# usb_to_rs232.net
KiCad netlist of a schematic drawn in Altium Designer
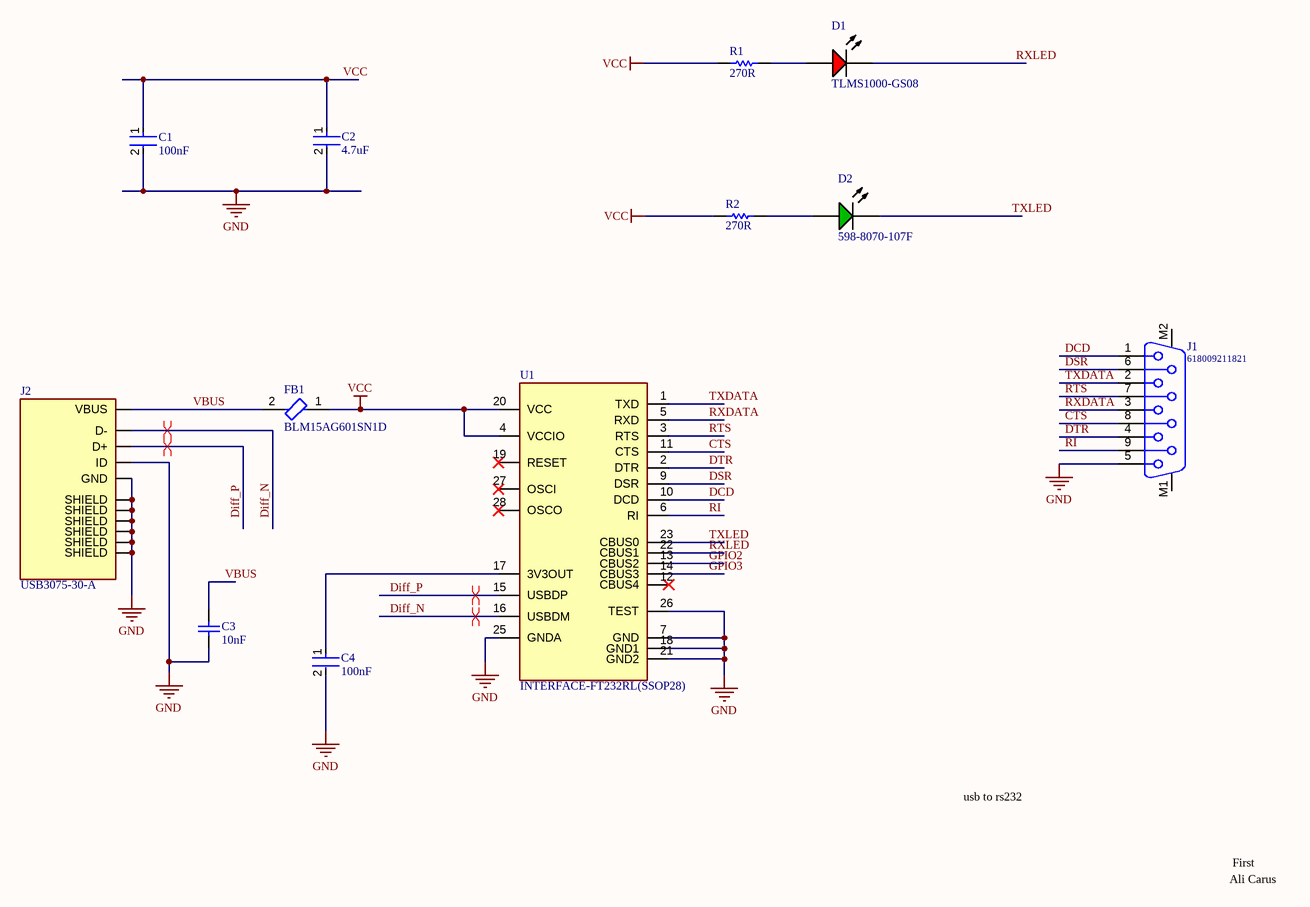
[diagram p0: usb_to_rs232.SchDoc]

(export (version "E")
  (design (tool "Eeschema 10.0.6"))
  (components
    (comp (ref "C1")
      (value "100nF")
      (footprint "FP-CGA3E-0_3-0_1-IPC_A")
      (description "Cap Ceramic 100nF 100V X7S 10% Pad SMD 0603 +125°C Automotive T/R")
      (fields (field (name "TOLERANCE") "10%"))
      (libsource (lib "Altium Content Vault") (part "b4654b650e69147ec39a6b967a45e02"))
    )
    (comp (ref "C2")
      (value "4.7uF")
      (footprint "FP-GRM188-0_2-MFG")
      (description "Chip Multilayer Ceramic Capacitors for General Purpose, 0603, 4.7uF, X5R, 15%, 10%, 35V")
      (fields (field (name "VOLTAGE") "35V") (field (name "TOLERANCE") "10%"))
      (libsource (lib "Altium Content Vault") (part "11868f565c42a9108669ba33697ecf6"))
    )
    (comp (ref "C3")
      (value "10nF")
      (footprint "CAPC1608X90X35ML10T15")
      (description "Chip Capacitor, 10 nF, +/- 10%, 50 V, -55 to 125 degC, 0603 (1608 Metric), RoHS, Tape and Reel")
      (fields (field (name "VOLTAGE") "50V") (field (name "TOLERANCE") "10%"))
      (libsource (lib "Altium Content Vault") (part "CAP-NP-2"))
    )
    (comp (ref "C4")
      (value "100nF")
      (footprint "FP-CGA3E-0_3-0_1-IPC_A")
      (description "Cap Ceramic 100nF 100V X7S 10% Pad SMD 0603 +125°C Automotive T/R")
      (fields (field (name "TOLERANCE") "10%"))
      (libsource (lib "Altium Content Vault") (part "b4654b650e69147ec39a6b967a45e02"))
    )
    (comp (ref "D1")
      (value "TLMS1000-GS08")
      (footprint "VISH-TLMS1000_V")
      (description "Low Current LED, 40 mW, 1.8 V, -40 to 100 degC, 2-Pin SMD (0603), RoHS, Tape and Reel")
      (fields (field (name "MANUFACTURER") "Vishay"))
      (libsource (lib "Altium Content Vault") (part "LED-RED-AK-2"))
    )
    (comp (ref "D2")
      (value "598-8070-107F")
      (footprint "DIAL-0603-2_V")
      (description "Single Color LED, 2 V, -30 to 85 degC, 2-Pin SMD (0603), RoHS, Tape and Reel")
      (fields (field (name "MANUFACTURER") "Dialight"))
      (libsource (lib "Altium Content Vault") (part "LED-GREEN-KA-2"))
    )
    (comp (ref "FB1")
      (value "BLM15AG601SN1D")
      (footprint "FP-BLM15-0_05-MFG")
      (description "Chip Ferrite Bead, 0402, 600Ω @ 100MHz, 0.52Ω, 25%, 300mA")
      (fields (field (name "TOLERANCE") "25%"))
      (libsource (lib "Altium Content Vault") (part "5f30dd21d616792df468990f7003faa"))
    )
    (comp (ref "J1")
      (value "618009211821")
      (footprint "618009211821")
      (description "WR-DSUB 8.08mm Female PCB Connector without Hex Screw, Angled, 9p")
      (fields (field (name "MANUFACTURER") "Wurth Elektronik"))
      (libsource (lib "usb_to_rs232") (part "618009211821"))
    )
    (comp (ref "J2")
      (value "USB3075-30-A")
      (footprint "GCT_USB3075-30-A")
      (description "USB - micro B USB 2.0 Receptacle Connector 5 Position Surface Mount, Right Angle; Through Hole")
      (fields
        (field (name "MF") "Global Connector Technology")
        (field (name "DIGI-KEY_PART_NUMBER") "2073-USB3075-30-ACT-ND")
      )
      (libsource (lib "usb_to_rs232") (part "USB3075-30-A"))
    )
    (comp (ref "R1")
      (value "270R")
      (footprint "RESC1608X55X30LL15T15")
      (fields (field (name "MANUFACTURER") "Panasonic") (field (name "PART NUMBER") "ERJ3EKF2700V"))
      (libsource (lib "Altium Content Vault") (part "RES"))
    )
    (comp (ref "R2")
      (value "270R")
      (footprint "RESC1608X55X30LL15T15")
      (fields (field (name "MANUFACTURER") "Panasonic") (field (name "PART NUMBER") "ERJ3EKF2700V"))
      (libsource (lib "Altium Content Vault") (part "RES"))
    )
    (comp (ref "U1")
      (value "INTERFACE-FT232RL(SSOP28)")
      (footprint "SSOP28-0.65-10.2X5.2MM")
      (description "USB Bridge, USB to UART USB 2.0 UART Interface 28-SSOP")
      (fields (field (name "MP") "FT232RL") (field (name "MF") "FTDI, Future"))
      (libsource (lib "usb_to_rs232") (part "INTERFACE-FT232RL(SSOP28)"))
    )
  )
  (nets
    (net (code "2") (name "/CTS") (class "Default")
      (node (ref "J1") (pin "8") (pinfunction "8_8") (pintype "passive"))
      (node (ref "U1") (pin "11") (pinfunction "CTS_11") (pintype "passive"))
    )
    (net (code "3") (name "/DCD") (class "Default")
      (node (ref "J1") (pin "1") (pinfunction "1_1") (pintype "passive"))
      (node (ref "U1") (pin "10") (pinfunction "DCD_10") (pintype "passive"))
    )
    (net (code "4") (name "/DSR") (class "Default")
      (node (ref "J1") (pin "6") (pinfunction "6_6") (pintype "passive"))
      (node (ref "U1") (pin "9") (pinfunction "DSR_9") (pintype "passive"))
    )
    (net (code "5") (name "/DTR") (class "Default")
      (node (ref "J1") (pin "4") (pinfunction "4_4") (pintype "passive"))
      (node (ref "U1") (pin "2") (pinfunction "DTR_2") (pintype "passive"))
    )
    (net (code "6") (name "/Diff_N") (class "Default")
      (node (ref "J2") (pin "2") (pinfunction "D-_2") (pintype "passive"))
      (node (ref "U1") (pin "16") (pinfunction "USBDM_16") (pintype "passive"))
    )
    (net (code "7") (name "/Diff_P") (class "Default")
      (node (ref "J2") (pin "3") (pinfunction "D+_3") (pintype "passive"))
      (node (ref "U1") (pin "15") (pinfunction "USBDP_15") (pintype "passive"))
    )
    (net (code "8") (name "/GPIO2") (class "Default")
      (node (ref "U1") (pin "13") (pinfunction "CBUS2_13") (pintype "passive"))
    )
    (net (code "9") (name "/GPIO3") (class "Default")
      (node (ref "U1") (pin "14") (pinfunction "CBUS3_14") (pintype "passive"))
    )
    (net (code "10") (name "/RI") (class "Default")
      (node (ref "J1") (pin "9") (pinfunction "9_9") (pintype "passive"))
      (node (ref "U1") (pin "6") (pinfunction "RI_6") (pintype "passive"))
    )
    (net (code "11") (name "/RTS") (class "Default")
      (node (ref "J1") (pin "7") (pinfunction "7_7") (pintype "passive"))
      (node (ref "U1") (pin "3") (pinfunction "RTS_3") (pintype "passive"))
    )
    (net (code "12") (name "/RXDATA") (class "Default")
      (node (ref "J1") (pin "3") (pinfunction "3_3") (pintype "passive"))
      (node (ref "U1") (pin "5") (pinfunction "RXD_5") (pintype "passive"))
    )
    (net (code "13") (name "/RXLED") (class "Default")
      (node (ref "D1") (pin "2") (pinfunction "K_2") (pintype "passive"))
      (node (ref "U1") (pin "22") (pinfunction "CBUS1_22") (pintype "passive"))
    )
    (net (code "14") (name "/TXDATA") (class "Default")
      (node (ref "J1") (pin "2") (pinfunction "2_2") (pintype "passive"))
      (node (ref "U1") (pin "1") (pinfunction "TXD_1") (pintype "passive"))
    )
    (net (code "15") (name "/TXLED") (class "Default")
      (node (ref "D2") (pin "1") (pinfunction "K_1") (pintype "passive"))
      (node (ref "U1") (pin "23") (pinfunction "CBUS0_23") (pintype "passive"))
    )
    (net (code "16") (name "/VBUS") (class "Default")
      (node (ref "C3") (pin "2") (pinfunction "2_2") (pintype "passive"))
      (node (ref "FB1") (pin "2") (pinfunction "2_2") (pintype "passive"))
      (node (ref "J2") (pin "1") (pinfunction "VBUS_1") (pintype "power_in"))
    )
    (net (code "17") (name "GND") (class "Default")
      (node (ref "C1") (pin "2") (pinfunction "2_2") (pintype "passive"))
      (node (ref "C2") (pin "2") (pinfunction "2_2") (pintype "passive"))
      (node (ref "C3") (pin "1") (pinfunction "1_1") (pintype "passive"))
      (node (ref "C4") (pin "2") (pinfunction "2_2") (pintype "passive"))
      (node (ref "J1") (pin "5") (pinfunction "5_5") (pintype "passive"))
      (node (ref "J2") (pin "4") (pinfunction "ID_4") (pintype "passive"))
      (node (ref "J2") (pin "5") (pinfunction "GND_5") (pintype "power_in"))
      (node (ref "J2") (pin "S1") (pinfunction "SHIELD_S1") (pintype "passive"))
      (node (ref "J2") (pin "S2") (pinfunction "SHIELD_S2") (pintype "passive"))
      (node (ref "J2") (pin "S3") (pinfunction "SHIELD_S3") (pintype "passive"))
      (node (ref "J2") (pin "S4") (pinfunction "SHIELD_S4") (pintype "passive"))
      (node (ref "J2") (pin "S5") (pinfunction "SHIELD_S5") (pintype "passive"))
      (node (ref "J2") (pin "S6") (pinfunction "SHIELD_S6") (pintype "passive"))
      (node (ref "U1") (pin "18") (pinfunction "GND1_18") (pintype "passive"))
      (node (ref "U1") (pin "21") (pinfunction "GND2_21") (pintype "passive"))
      (node (ref "U1") (pin "25") (pinfunction "GNDA_25") (pintype "passive"))
      (node (ref "U1") (pin "26") (pinfunction "TEST_26") (pintype "passive"))
      (node (ref "U1") (pin "7") (pinfunction "GND_7") (pintype "passive"))
    )
    (net (code "18") (name "Net-(D1-A)") (class "Default")
      (node (ref "D1") (pin "1") (pinfunction "A_1") (pintype "passive"))
      (node (ref "R1") (pin "1") (pinfunction "1_1") (pintype "passive"))
    )
    (net (code "19") (name "Net-(D2-A)") (class "Default")
      (node (ref "D2") (pin "2") (pinfunction "A_2") (pintype "passive"))
      (node (ref "R2") (pin "1") (pinfunction "1_1") (pintype "passive"))
    )
    (net (code "20") (name "Net-(U1-3V3OUT)") (class "Default")
      (node (ref "C4") (pin "1") (pinfunction "1_1") (pintype "passive"))
      (node (ref "U1") (pin "17") (pinfunction "3V3OUT_17") (pintype "passive"))
    )
    (net (code "21") (name "VCC") (class "Default")
      (node (ref "C1") (pin "1") (pinfunction "1_1") (pintype "passive"))
      (node (ref "C2") (pin "1") (pinfunction "1_1") (pintype "passive"))
      (node (ref "FB1") (pin "1") (pinfunction "1_1") (pintype "passive"))
      (node (ref "R1") (pin "2") (pinfunction "2_2") (pintype "passive"))
      (node (ref "R2") (pin "2") (pinfunction "2_2") (pintype "passive"))
      (node (ref "U1") (pin "20") (pinfunction "VCC_20") (pintype "passive"))
      (node (ref "U1") (pin "4") (pinfunction "VCCIO_4") (pintype "passive"))
    )
    (net (code "22") (name "unconnected-(J1-PadM1)") (class "Default")
      (node (ref "J1") (pin "M1") (pinfunction "M1_M1") (pintype "passive"))
    )
    (net (code "23") (name "unconnected-(J1-PadM2)") (class "Default")
      (node (ref "J1") (pin "M2") (pinfunction "M2_M2") (pintype "passive"))
    )
    (net (code "24") (name "unconnected-(U1-CBUS4-Pad12)") (class "Default")
      (node (ref "U1") (pin "12") (pinfunction "CBUS4_12") (pintype "passive+no_connect"))
    )
    (net (code "25") (name "unconnected-(U1-OSCI-Pad27)") (class "Default")
      (node (ref "U1") (pin "27") (pinfunction "OSCI_27") (pintype "passive+no_connect"))
    )
    (net (code "26") (name "unconnected-(U1-OSCO-Pad28)") (class "Default")
      (node (ref "U1") (pin "28") (pinfunction "OSCO_28") (pintype "passive+no_connect"))
    )
    (net (code "27") (name "unconnected-(U1-RESET-Pad19)") (class "Default")
      (node (ref "U1") (pin "19") (pinfunction "RESET_19") (pintype "passive+no_connect"))
    )
  )
)
